# 01b3_HID_Processor_W_BT.net
KiCad netlist of a schematic drawn in Altium Designer
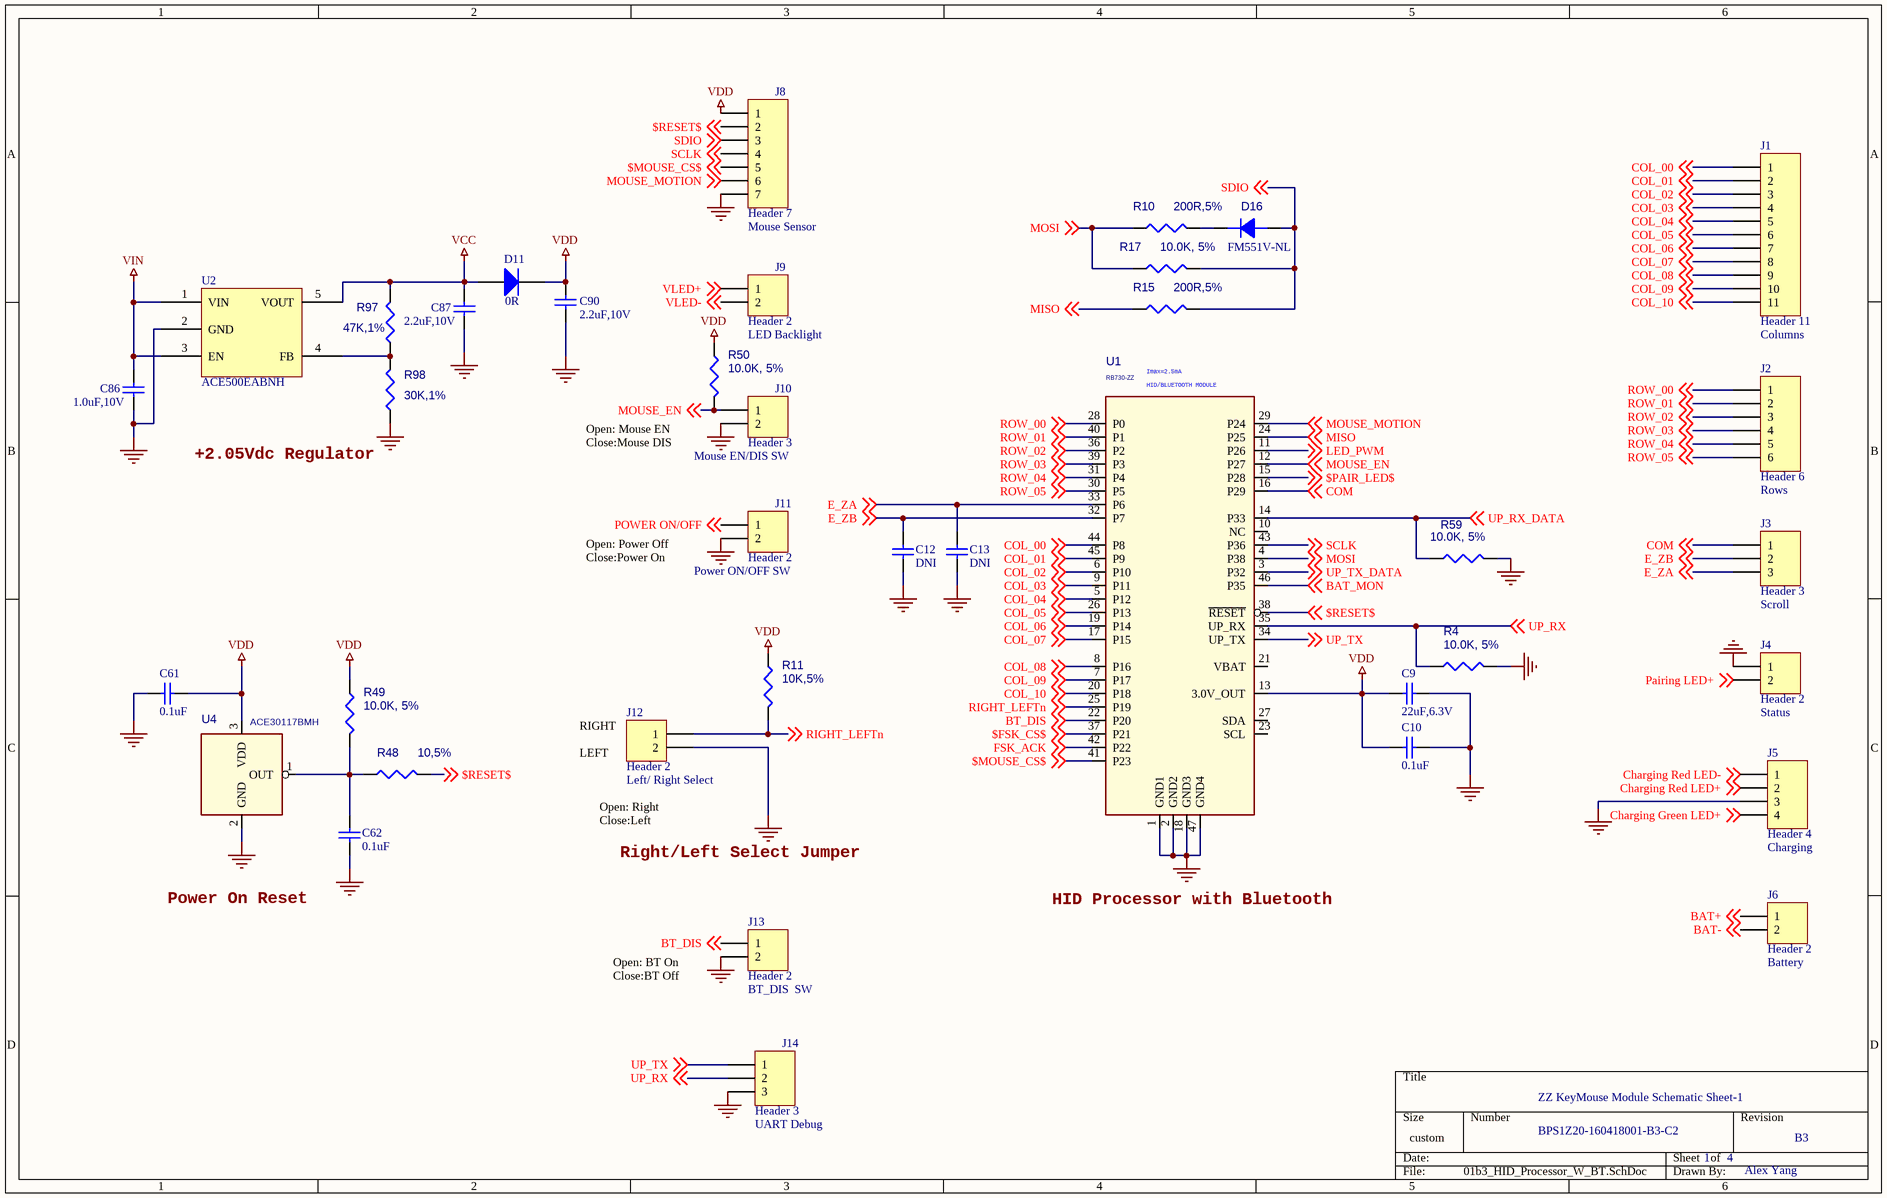
[diagram p0: 01b3_HID_Processor_W_BT.SchDoc]

(export (version "E")
  (design (tool "Eeschema 10.0.6"))
  (components
    (comp (ref "C9")
      (value "22uF,6.3V")
      (footprint "MIN0805")
      (description "Capacitor")
      (libsource (lib "Miscellaneous Devices") (part "Cap"))
    )
    (comp (ref "C10")
      (value "0.1uF")
      (footprint "0603")
      (description "Capacitor")
      (libsource (lib "Miscellaneous Devices") (part "Cap"))
    )
    (comp (ref "C12")
      (value "DNI")
      (footprint "0603-2")
      (description "Capacitor")
      (libsource (lib "Miscellaneous Devices") (part "Cap"))
    )
    (comp (ref "C13")
      (value "DNI")
      (footprint "0603-2")
      (description "Capacitor")
      (libsource (lib "Miscellaneous Devices") (part "Cap"))
    )
    (comp (ref "C61")
      (value "0.1uF")
      (footprint "0603")
      (description "Capacitor")
      (libsource (lib "Miscellaneous Devices") (part "Cap"))
    )
    (comp (ref "C62")
      (value "0.1uF")
      (footprint "0603")
      (description "Capacitor")
      (libsource (lib "Miscellaneous Devices") (part "Cap"))
    )
    (comp (ref "C86")
      (value "1.0uF,10V")
      (footprint "0603")
      (description "Capacitor")
      (libsource (lib "Miscellaneous Devices") (part "Cap"))
    )
    (comp (ref "C87")
      (value "2.2uF,10V")
      (footprint "0603")
      (description "Capacitor")
      (libsource (lib "Miscellaneous Devices") (part "Cap"))
    )
    (comp (ref "C90")
      (value "2.2uF,10V")
      (footprint "0603")
      (description "Capacitor")
      (libsource (lib "Miscellaneous Devices") (part "Cap"))
    )
    (comp (ref "D11")
      (value "0R")
      (footprint "SM08-DIODE")
      (description "Default Diode")
      (fields (field (name "PUBLISHER") "Altium Limited"))
      (libsource (lib "Miscellaneous Devices") (part "Diode"))
    )
    (comp (ref "D16")
      (value "DIODE")
      (footprint "FM551-NL")
      (fields (field (name "ALTIUM_UNNAMED_1") "FM551V-NL"))
      (libsource (lib "L MAIN_Library") (part "DIODE"))
    )
    (comp (ref "J1")
      (value "Header 11")
      (footprint "HDR1X11H")
      (description "Header, 11-Pin, Right Angle")
      (fields (field (name "PUBLISHER") "Altium Limited"))
      (libsource (lib "Miscellaneous Connectors") (part "Header 11H"))
    )
    (comp (ref "J2")
      (value "Header 6")
      (footprint "HDR1X6H")
      (description "Header, 6-Pin, Right Angle")
      (fields (field (name "PUBLISHER") "Altium Limited"))
      (libsource (lib "Miscellaneous Connectors") (part "Header 6H"))
    )
    (comp (ref "J3")
      (value "Header 3")
      (footprint "HDR1X3H")
      (description "Header, 3-Pin")
      (fields (field (name "PUBLISHER") "Altium Limited"))
      (libsource (lib "Miscellaneous Connectors") (part "Header 3"))
    )
    (comp (ref "J4")
      (value "Header 2")
      (footprint "HDR1X2H")
      (description "Header, 2-Pin")
      (fields (field (name "PUBLISHER") "Altium Limited"))
      (libsource (lib "Miscellaneous Connectors") (part "Header 2"))
    )
    (comp (ref "J5")
      (value "Header 4")
      (footprint "HDR1X4H")
      (description "Header, 4-Pin")
      (fields (field (name "PUBLISHER") "Altium Limited"))
      (libsource (lib "Miscellaneous Connectors") (part "Header 4"))
    )
    (comp (ref "J6")
      (value "Header 2")
      (footprint "HDR1X2H")
      (description "Header, 2-Pin")
      (fields (field (name "PUBLISHER") "Altium Limited"))
      (libsource (lib "Miscellaneous Connectors") (part "Header 2"))
    )
    (comp (ref "J8")
      (value "Header 7")
      (footprint "HDR1X7h")
      (description "Header, 7-Pin")
      (fields (field (name "PUBLISHER") "Altium Limited"))
      (libsource (lib "Miscellaneous Connectors") (part "Header 7"))
    )
    (comp (ref "J9")
      (value "Header 2")
      (footprint "HDR1X2h")
      (description "Header, 2-Pin")
      (fields (field (name "PUBLISHER") "Altium Limited"))
      (libsource (lib "Miscellaneous Connectors") (part "Header 2"))
    )
    (comp (ref "J10")
      (value "Header 3")
      (footprint "HDR1X2h")
      (description "Header, 2-Pin")
      (fields (field (name "PUBLISHER") "Altium Limited"))
      (libsource (lib "Miscellaneous Connectors") (part "Header 2"))
    )
    (comp (ref "J11")
      (value "Header 2")
      (footprint "HDR1X2h")
      (description "Header, 2-Pin")
      (fields (field (name "PUBLISHER") "Altium Limited"))
      (libsource (lib "Miscellaneous Connectors") (part "Header 2"))
    )
    (comp (ref "J12")
      (value "Header 2")
      (footprint "HDR1X2")
      (description "Header, 2-Pin")
      (fields (field (name "PUBLISHER") "Altium Limited"))
      (libsource (lib "") (part "Header 2_1"))
    )
    (comp (ref "J13")
      (value "Header 2")
      (footprint "HDR1X2H")
      (description "Header, 2-Pin")
      (fields (field (name "PUBLISHER") "Altium Limited"))
      (libsource (lib "Miscellaneous Connectors") (part "Header 2"))
    )
    (comp (ref "J14")
      (value "Header 3")
      (footprint "HDR1X3")
      (description "Header, 3-Pin")
      (fields (field (name "PUBLISHER") "Altium Limited"))
      (libsource (lib "Miscellaneous Connectors") (part "Header 3"))
    )
    (comp (ref "R4") (value "10.0K, 5%") (footprint "0402") (libsource (lib "*") (part "R")))
    (comp (ref "R10") (value "200R,5%") (footprint "0402") (libsource (lib "*") (part "R")))
    (comp (ref "R11") (value "10K,5%") (footprint "0402") (libsource (lib "*") (part "R")))
    (comp (ref "R15") (value "200R,5%") (footprint "0402") (libsource (lib "*") (part "R")))
    (comp (ref "R17") (value "10.0K, 5%") (footprint "0402") (libsource (lib "*") (part "R")))
    (comp (ref "R48") (value "10,5%") (footprint "0402") (libsource (lib "*") (part "R")))
    (comp (ref "R49") (value "10.0K, 5%") (footprint "0402") (libsource (lib "*") (part "R")))
    (comp (ref "R50") (value "10.0K, 5%") (footprint "0402") (libsource (lib "*") (part "R")))
    (comp (ref "R59") (value "10.0K, 5%") (footprint "0402") (libsource (lib "*") (part "R")))
    (comp (ref "R97") (value "47K,1%") (footprint "0402") (libsource (lib "*") (part "R")))
    (comp (ref "R98") (value "30K,1%") (footprint "0402") (libsource (lib "*") (part "R")))
    (comp (ref "U1")
      (value "RB730-ZZ")
      (footprint "RB730_SMD_MOD")
      (libsource (lib "*") (part "HID/BLUETOOTH MODULE_0"))
    )
    (comp (ref "U2")
      (value "ACE500EABNH")
      (footprint "SOT23-5")
      (fields (field (name "PUBLISHER") "Altium Limited"))
      (libsource (lib "ZZ KeyMouse Module") (part "ACE500EABNH"))
    )
    (comp (ref "U4") (value "ACE30117BMH") (footprint "SOT23") (libsource (lib "*") (part "STM1061N19WX6F")))
  )
  (nets
    (net (code "1") (name "$FSK_CS$") (class "Default")
      (node (ref "U1") (pin "37") (pinfunction "P21_37") (pintype "passive"))
    )
    (net (code "2") (name "$MOUSE_CS$") (class "Default")
      (node (ref "J8") (pin "5") (pinfunction "5_5") (pintype "passive"))
      (node (ref "U1") (pin "41") (pinfunction "P23_41") (pintype "passive"))
    )
    (net (code "3") (name "$PAIR_LED$") (class "Default")
      (node (ref "U1") (pin "15") (pinfunction "P28_15") (pintype "passive"))
    )
    (net (code "4") (name "$RESET$") (class "Default")
      (node (ref "J8") (pin "2") (pinfunction "2_2") (pintype "passive"))
      (node (ref "R48") (pin "2") (pinfunction "2_2") (pintype "passive"))
      (node (ref "U1") (pin "38") (pinfunction "~{RESET}_38") (pintype "passive"))
    )
    (net (code "5") (name "BAT+") (class "Default")
      (node (ref "J6") (pin "1") (pinfunction "1_1") (pintype "passive"))
    )
    (net (code "6") (name "BAT-") (class "Default")
      (node (ref "J6") (pin "2") (pinfunction "2_2") (pintype "passive"))
    )
    (net (code "7") (name "BAT_MON") (class "Default")
      (node (ref "U1") (pin "46") (pinfunction "P35_46") (pintype "passive"))
    )
    (net (code "8") (name "BT_DIS") (class "Default")
      (node (ref "J13") (pin "1") (pinfunction "1_1") (pintype "passive"))
      (node (ref "U1") (pin "22") (pinfunction "P20_22") (pintype "passive"))
    )
    (net (code "9") (name "COL_00") (class "Default")
      (node (ref "J1") (pin "1") (pinfunction "1_1") (pintype "passive"))
      (node (ref "U1") (pin "44") (pinfunction "P8_44") (pintype "passive"))
    )
    (net (code "10") (name "COL_01") (class "Default")
      (node (ref "J1") (pin "2") (pinfunction "2_2") (pintype "passive"))
      (node (ref "U1") (pin "45") (pinfunction "P9_45") (pintype "passive"))
    )
    (net (code "11") (name "COL_02") (class "Default")
      (node (ref "J1") (pin "3") (pinfunction "3_3") (pintype "passive"))
      (node (ref "U1") (pin "6") (pinfunction "P10_6") (pintype "passive"))
    )
    (net (code "12") (name "COL_03") (class "Default")
      (node (ref "J1") (pin "4") (pinfunction "4_4") (pintype "passive"))
      (node (ref "U1") (pin "9") (pinfunction "P11_9") (pintype "passive"))
    )
    (net (code "13") (name "COL_04") (class "Default")
      (node (ref "J1") (pin "5") (pinfunction "5_5") (pintype "passive"))
      (node (ref "U1") (pin "5") (pinfunction "P12_5") (pintype "passive"))
    )
    (net (code "14") (name "COL_05") (class "Default")
      (node (ref "J1") (pin "6") (pinfunction "6_6") (pintype "passive"))
      (node (ref "U1") (pin "26") (pinfunction "P13_26") (pintype "passive"))
    )
    (net (code "15") (name "COL_06") (class "Default")
      (node (ref "J1") (pin "7") (pinfunction "7_7") (pintype "passive"))
      (node (ref "U1") (pin "19") (pinfunction "P14_19") (pintype "passive"))
    )
    (net (code "16") (name "COL_07") (class "Default")
      (node (ref "J1") (pin "8") (pinfunction "8_8") (pintype "passive"))
      (node (ref "U1") (pin "17") (pinfunction "P15_17") (pintype "passive"))
    )
    (net (code "17") (name "COL_08") (class "Default")
      (node (ref "J1") (pin "9") (pinfunction "9_9") (pintype "passive"))
      (node (ref "U1") (pin "8") (pinfunction "P16_8") (pintype "passive"))
    )
    (net (code "18") (name "COL_09") (class "Default")
      (node (ref "J1") (pin "10") (pinfunction "10_10") (pintype "passive"))
      (node (ref "U1") (pin "7") (pinfunction "P17_7") (pintype "passive"))
    )
    (net (code "19") (name "COL_10") (class "Default")
      (node (ref "J1") (pin "11") (pinfunction "11_11") (pintype "passive"))
      (node (ref "U1") (pin "20") (pinfunction "P18_20") (pintype "passive"))
    )
    (net (code "20") (name "COM") (class "Default")
      (node (ref "J3") (pin "1") (pinfunction "1_1") (pintype "passive"))
      (node (ref "U1") (pin "16") (pinfunction "P29_16") (pintype "passive"))
    )
    (net (code "21") (name "Charging Green LED+") (class "Default")
      (node (ref "J5") (pin "4") (pinfunction "4_4") (pintype "passive"))
    )
    (net (code "22") (name "Charging Red LED+") (class "Default")
      (node (ref "J5") (pin "2") (pinfunction "2_2") (pintype "passive"))
    )
    (net (code "23") (name "Charging Red LED-") (class "Default")
      (node (ref "J5") (pin "1") (pinfunction "1_1") (pintype "passive"))
    )
    (net (code "24") (name "E_ZA") (class "Default")
      (node (ref "C13") (pin "1") (pinfunction "1_1") (pintype "passive"))
      (node (ref "J3") (pin "3") (pinfunction "3_3") (pintype "passive"))
      (node (ref "U1") (pin "33") (pinfunction "P6_33") (pintype "passive"))
    )
    (net (code "25") (name "E_ZB") (class "Default")
      (node (ref "C12") (pin "1") (pinfunction "1_1") (pintype "passive"))
      (node (ref "J3") (pin "2") (pinfunction "2_2") (pintype "passive"))
      (node (ref "U1") (pin "32") (pinfunction "P7_32") (pintype "passive"))
    )
    (net (code "26") (name "FSK_ACK") (class "Default")
      (node (ref "U1") (pin "42") (pinfunction "P22_42") (pintype "passive"))
    )
    (net (code "27") (name "GND") (class "Default")
      (node (ref "C10") (pin "1") (pinfunction "1_1") (pintype "passive"))
      (node (ref "C12") (pin "2") (pinfunction "2_2") (pintype "passive"))
      (node (ref "C13") (pin "2") (pinfunction "2_2") (pintype "passive"))
      (node (ref "C61") (pin "2") (pinfunction "2_2") (pintype "passive"))
      (node (ref "C62") (pin "2") (pinfunction "2_2") (pintype "passive"))
      (node (ref "C86") (pin "1") (pinfunction "1_1") (pintype "passive"))
      (node (ref "C87") (pin "1") (pinfunction "1_1") (pintype "passive"))
      (node (ref "C9") (pin "1") (pinfunction "1_1") (pintype "passive"))
      (node (ref "C90") (pin "1") (pinfunction "1_1") (pintype "passive"))
      (node (ref "J10") (pin "2") (pinfunction "2_2") (pintype "passive"))
      (node (ref "J11") (pin "2") (pinfunction "2_2") (pintype "passive"))
      (node (ref "J12") (pin "2") (pinfunction "2_2") (pintype "passive"))
      (node (ref "J13") (pin "2") (pinfunction "2_2") (pintype "passive"))
      (node (ref "J14") (pin "3") (pinfunction "3_3") (pintype "passive"))
      (node (ref "J4") (pin "1") (pinfunction "1_1") (pintype "passive"))
      (node (ref "J5") (pin "3") (pinfunction "3_3") (pintype "passive"))
      (node (ref "J8") (pin "7") (pinfunction "7_7") (pintype "passive"))
      (node (ref "R4") (pin "2") (pinfunction "2_2") (pintype "passive"))
      (node (ref "R59") (pin "2") (pinfunction "2_2") (pintype "passive"))
      (node (ref "R98") (pin "2") (pinfunction "2_2") (pintype "passive"))
      (node (ref "U1") (pin "1") (pinfunction "GND1_1") (pintype "passive"))
      (node (ref "U1") (pin "18") (pinfunction "GND3_18") (pintype "passive"))
      (node (ref "U1") (pin "2") (pinfunction "GND2_2") (pintype "passive"))
      (node (ref "U1") (pin "47") (pinfunction "GND4_47") (pintype "passive"))
      (node (ref "U2") (pin "2") (pinfunction "GND_2") (pintype "passive"))
      (node (ref "U4") (pin "2") (pinfunction "GND_2") (pintype "passive"))
    )
    (net (code "28") (name "LED_PWM") (class "Default")
      (node (ref "U1") (pin "11") (pinfunction "P26_11") (pintype "passive"))
    )
    (net (code "29") (name "MISO") (class "Default")
      (node (ref "R15") (pin "1") (pinfunction "1_1") (pintype "passive"))
      (node (ref "U1") (pin "24") (pinfunction "P25_24") (pintype "passive"))
    )
    (net (code "30") (name "MOSI") (class "Default")
      (node (ref "R10") (pin "1") (pinfunction "1_1") (pintype "passive"))
      (node (ref "R17") (pin "1") (pinfunction "1_1") (pintype "passive"))
      (node (ref "U1") (pin "4") (pinfunction "P38_4") (pintype "passive"))
    )
    (net (code "31") (name "MOUSE_EN") (class "Default")
      (node (ref "J10") (pin "1") (pinfunction "1_1") (pintype "passive"))
      (node (ref "R50") (pin "2") (pinfunction "2_2") (pintype "passive"))
      (node (ref "U1") (pin "12") (pinfunction "P27_12") (pintype "passive"))
    )
    (net (code "32") (name "MOUSE_MOTION") (class "Default")
      (node (ref "J8") (pin "6") (pinfunction "6_6") (pintype "passive"))
      (node (ref "U1") (pin "29") (pinfunction "P24_29") (pintype "passive"))
    )
    (net (code "33") (name "Net-(D16-K)") (class "Default")
      (node (ref "D16") (pin "2") (pinfunction "K_2") (pintype "passive"))
      (node (ref "R10") (pin "2") (pinfunction "2_2") (pintype "passive"))
    )
    (net (code "34") (name "Net-(U2-FB)") (class "Default")
      (node (ref "R97") (pin "2") (pinfunction "2_2") (pintype "passive"))
      (node (ref "R98") (pin "1") (pinfunction "1_1") (pintype "passive"))
      (node (ref "U2") (pin "4") (pinfunction "FB_4") (pintype "passive"))
    )
    (net (code "35") (name "Net-(U4-OUT)") (class "Default")
      (node (ref "C62") (pin "1") (pinfunction "1_1") (pintype "passive"))
      (node (ref "R48") (pin "1") (pinfunction "1_1") (pintype "passive"))
      (node (ref "R49") (pin "2") (pinfunction "2_2") (pintype "passive"))
      (node (ref "U4") (pin "1") (pinfunction "OUT_1") (pintype "passive"))
    )
    (net (code "36") (name "POWER ON{slash}OFF") (class "Default")
      (node (ref "J11") (pin "1") (pinfunction "1_1") (pintype "passive"))
    )
    (net (code "37") (name "Pairing LED+") (class "Default")
      (node (ref "J4") (pin "2") (pinfunction "2_2") (pintype "passive"))
    )
    (net (code "38") (name "RIGHT_LEFTn") (class "Default")
      (node (ref "J12") (pin "1") (pinfunction "1_1") (pintype "passive"))
      (node (ref "R11") (pin "2") (pinfunction "2_2") (pintype "passive"))
      (node (ref "U1") (pin "25") (pinfunction "P19_25") (pintype "passive"))
    )
    (net (code "39") (name "ROW_00") (class "Default")
      (node (ref "J2") (pin "1") (pinfunction "1_1") (pintype "passive"))
      (node (ref "U1") (pin "28") (pinfunction "P0_28") (pintype "passive"))
    )
    (net (code "40") (name "ROW_01") (class "Default")
      (node (ref "J2") (pin "2") (pinfunction "2_2") (pintype "passive"))
      (node (ref "U1") (pin "40") (pinfunction "P1_40") (pintype "passive"))
    )
    (net (code "41") (name "ROW_02") (class "Default")
      (node (ref "J2") (pin "3") (pinfunction "3_3") (pintype "passive"))
      (node (ref "U1") (pin "36") (pinfunction "P2_36") (pintype "passive"))
    )
    (net (code "42") (name "ROW_03") (class "Default")
      (node (ref "J2") (pin "4") (pinfunction "4_4") (pintype "passive"))
      (node (ref "U1") (pin "39") (pinfunction "P3_39") (pintype "passive"))
    )
    (net (code "43") (name "ROW_04") (class "Default")
      (node (ref "J2") (pin "5") (pinfunction "5_5") (pintype "passive"))
      (node (ref "U1") (pin "31") (pinfunction "P4_31") (pintype "passive"))
    )
    (net (code "44") (name "ROW_05") (class "Default")
      (node (ref "J2") (pin "6") (pinfunction "6_6") (pintype "passive"))
      (node (ref "U1") (pin "30") (pinfunction "P5_30") (pintype "passive"))
    )
    (net (code "45") (name "SCLK") (class "Default")
      (node (ref "J8") (pin "4") (pinfunction "4_4") (pintype "passive"))
      (node (ref "U1") (pin "43") (pinfunction "P36_43") (pintype "passive"))
    )
    (net (code "46") (name "SDIO") (class "Default")
      (node (ref "D16") (pin "1") (pinfunction "A_1") (pintype "passive"))
      (node (ref "J8") (pin "3") (pinfunction "3_3") (pintype "passive"))
      (node (ref "R15") (pin "2") (pinfunction "2_2") (pintype "passive"))
      (node (ref "R17") (pin "2") (pinfunction "2_2") (pintype "passive"))
    )
    (net (code "47") (name "UP_RX") (class "Default")
      (node (ref "J14") (pin "2") (pinfunction "2_2") (pintype "passive"))
      (node (ref "R4") (pin "1") (pinfunction "1_1") (pintype "passive"))
      (node (ref "U1") (pin "35") (pinfunction "UP_RX_35") (pintype "passive"))
    )
    (net (code "48") (name "UP_RX_DATA") (class "Default")
      (node (ref "R59") (pin "1") (pinfunction "1_1") (pintype "passive"))
      (node (ref "U1") (pin "14") (pinfunction "P33_14") (pintype "passive"))
    )
    (net (code "49") (name "UP_TX") (class "Default")
      (node (ref "J14") (pin "1") (pinfunction "1_1") (pintype "passive"))
      (node (ref "U1") (pin "34") (pinfunction "UP_TX_34") (pintype "passive"))
    )
    (net (code "50") (name "UP_TX_DATA") (class "Default")
      (node (ref "U1") (pin "3") (pinfunction "P32_3") (pintype "passive"))
    )
    (net (code "51") (name "VCC") (class "Default")
      (node (ref "C87") (pin "2") (pinfunction "2_2") (pintype "passive"))
      (node (ref "D11") (pin "1") (pinfunction "A_1") (pintype "passive"))
      (node (ref "R97") (pin "1") (pinfunction "1_1") (pintype "passive"))
      (node (ref "U2") (pin "5") (pinfunction "VOUT_5") (pintype "passive"))
    )
    (net (code "52") (name "VDD") (class "Default")
      (node (ref "C10") (pin "2") (pinfunction "2_2") (pintype "passive"))
      (node (ref "C61") (pin "1") (pinfunction "1_1") (pintype "passive"))
      (node (ref "C9") (pin "2") (pinfunction "2_2") (pintype "passive"))
      (node (ref "C90") (pin "2") (pinfunction "2_2") (pintype "passive"))
      (node (ref "D11") (pin "2") (pinfunction "K_2") (pintype "passive"))
      (node (ref "J8") (pin "1") (pinfunction "1_1") (pintype "passive"))
      (node (ref "R11") (pin "1") (pinfunction "1_1") (pintype "passive"))
      (node (ref "R49") (pin "1") (pinfunction "1_1") (pintype "passive"))
      (node (ref "R50") (pin "1") (pinfunction "1_1") (pintype "passive"))
      (node (ref "U1") (pin "13") (pinfunction "3.0V_OUT_13") (pintype "passive"))
      (node (ref "U4") (pin "3") (pinfunction "VDD_3") (pintype "power_in"))
    )
    (net (code "53") (name "VIN") (class "Default")
      (node (ref "C86") (pin "2") (pinfunction "2_2") (pintype "passive"))
      (node (ref "U2") (pin "1") (pinfunction "VIN_1") (pintype "passive"))
      (node (ref "U2") (pin "3") (pinfunction "EN_3") (pintype "passive"))
    )
    (net (code "54") (name "VLED+") (class "Default")
      (node (ref "J9") (pin "1") (pinfunction "1_1") (pintype "passive"))
    )
    (net (code "55") (name "VLED-") (class "Default")
      (node (ref "J9") (pin "2") (pinfunction "2_2") (pintype "passive"))
    )
    (net (code "56") (name "unconnected-(U1-NC-Pad10)") (class "Default")
      (node (ref "U1") (pin "10") (pinfunction "NC_10") (pintype "passive"))
    )
    (net (code "57") (name "unconnected-(U1-SCL-Pad23)") (class "Default")
      (node (ref "U1") (pin "23") (pinfunction "SCL_23") (pintype "passive"))
    )
    (net (code "58") (name "unconnected-(U1-SDA-Pad27)") (class "Default")
      (node (ref "U1") (pin "27") (pinfunction "SDA_27") (pintype "passive"))
    )
    (net (code "59") (name "unconnected-(U1-VBAT-Pad21)") (class "Default")
      (node (ref "U1") (pin "21") (pinfunction "VBAT_21") (pintype "passive"))
    )
  )
)
